# e-ink-clock.net
KiCad netlist of a schematic drawn in EAGLE
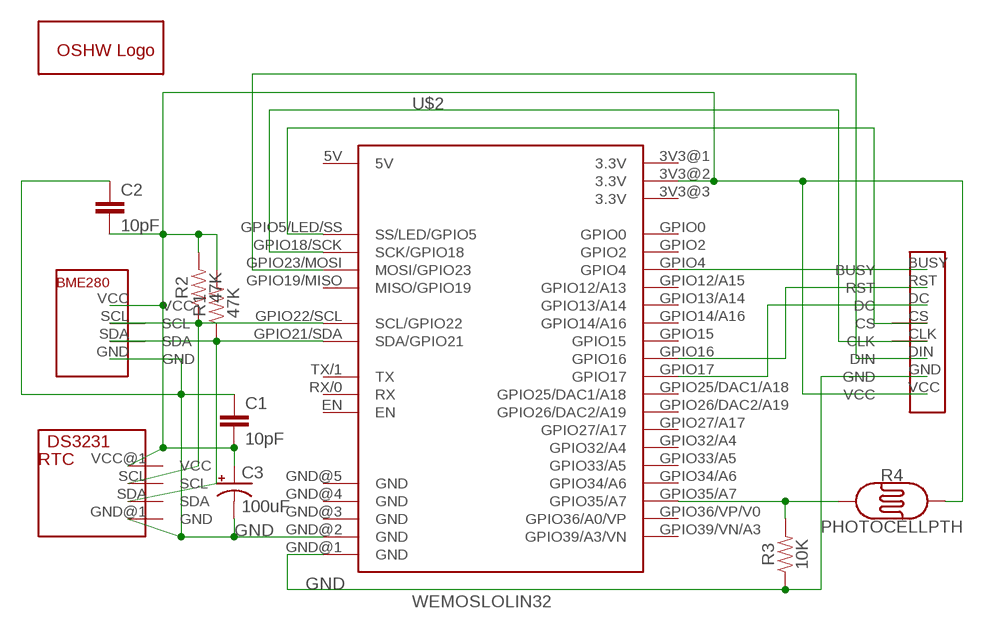
[diagram p0: schematic, sheet 1]

(export (version "E")
  (design (tool "Eeschema 10.0.6"))
  (components
    (comp (ref "C1")
      (value "10pF")
      (footprint "eagle-import:CAP-PTH-SMALL2")
      (libsource (lib "eagle-import") (part "CAPPTH2"))
    )
    (comp (ref "C2")
      (value "10pF")
      (footprint "eagle-import:CAP-PTH-SMALL2")
      (libsource (lib "eagle-import") (part "CAPPTH2"))
    )
    (comp (ref "C3")
      (value "100uF")
      (footprint "eagle-import:CPOL-RADIAL-2.5MM-6.5MM")
      (libsource (lib "eagle-import") (part "100UF-POLAR-RADIAL-2.5MM-25V-20%"))
    )
    (comp (ref "GOLD_ORB_SM1")
      (value "OSHWLOGOLOGO16MM")
      (footprint "eagle-import:OSHW_16MM")
      (libsource (lib "eagle-import") (part "OSHWLOGOLOGO16MM"))
    )
    (comp (ref "R1")
      (value "47K")
      (footprint "eagle-import:AXIAL-0.3")
      (libsource (lib "eagle-import") (part "RESISTORAXIAL-0.3"))
    )
    (comp (ref "R2")
      (value "47K")
      (footprint "eagle-import:AXIAL-0.3")
      (libsource (lib "eagle-import") (part "RESISTORAXIAL-0.3"))
    )
    (comp (ref "R3")
      (value "10K")
      (footprint "eagle-import:AXIAL-0.3")
      (libsource (lib "eagle-import") (part "RESISTORAXIAL-0.3"))
    )
    (comp (ref "R4")
      (value "PHOTOCELLPTH")
      (footprint "eagle-import:PHOTOCELL")
      (libsource (lib "eagle-import") (part "PHOTOCELLPTH"))
    )
    (comp (ref "U$1")
      (value "WAVESHAREE-INK")
      (footprint "eagle-import:WAVESHARE-EINK")
      (libsource (lib "eagle-import") (part "WAVESHAREE-INK"))
    )
    (comp (ref "U$2")
      (value "WEMOSLOLIN32")
      (footprint "eagle-import:LOLIN32VAR1")
      (libsource (lib "eagle-import") (part "WEMOSLOLIN32"))
    )
    (comp (ref "U$3")
      (value "BME280BREAKOUTBME280")
      (footprint "eagle-import:HDRV4W64P254_1X4_1016X508X838B")
      (libsource (lib "eagle-import") (part "BME280BREAKOUTBME280"))
    )
    (comp (ref "U$4")
      (value "DS3231BREAKOUT")
      (footprint "eagle-import:DS3231BREAKOUT")
      (libsource (lib "eagle-import") (part "DS3231BREAKOUT"))
    )
  )
  (nets
    (net (code "1") (name "/3.3V") (class "Default")
      (node (ref "U$2") (pin "3V3@3") (pinfunction "3.3V_3V3@3") (pintype "power_in"))
    )
    (net (code "2") (name "/5V") (class "Default")
      (node (ref "U$2") (pin "5V") (pinfunction "5V_5V") (pintype "power_in"))
    )
    (net (code "3") (name "/GND") (class "Default")
      (node (ref "C1") (pin "1") (pinfunction "1_1") (pintype "passive"))
      (node (ref "C2") (pin "1") (pinfunction "1_1") (pintype "passive"))
      (node (ref "C3") (pin "2") (pinfunction "-_2") (pintype "passive"))
      (node (ref "R3") (pin "P$1") (pinfunction "1_P$1") (pintype "passive"))
      (node (ref "U$1") (pin "GND") (pinfunction "GND_GND") (pintype "power_in"))
      (node (ref "U$2") (pin "GND@1") (pinfunction "GND_GND@1") (pintype "power_in"))
      (node (ref "U$2") (pin "GND@2") (pinfunction "GND_GND@2") (pintype "bidirectional"))
      (node (ref "U$3") (pin "GND") (pinfunction "GND_GND") (pintype "power_in"))
      (node (ref "U$4") (pin "GND@1") (pinfunction "GND_GND@1") (pintype "power_in"))
    )
    (net (code "4") (name "Net-(C3-+)") (class "Default")
      (node (ref "C1") (pin "2") (pinfunction "2_2") (pintype "passive"))
      (node (ref "C2") (pin "2") (pinfunction "2_2") (pintype "passive"))
      (node (ref "C3") (pin "1") (pinfunction "+_1") (pintype "passive"))
      (node (ref "R1") (pin "P$2") (pinfunction "2_P$2") (pintype "passive"))
      (node (ref "R2") (pin "P$2") (pinfunction "2_P$2") (pintype "passive"))
      (node (ref "R4") (pin "2") (pinfunction "P$2_2") (pintype "bidirectional"))
      (node (ref "U$1") (pin "VCC") (pinfunction "VCC_VCC") (pintype "power_in"))
      (node (ref "U$2") (pin "3V3@2") (pinfunction "3.3V_3V3@2") (pintype "bidirectional"))
      (node (ref "U$3") (pin "VCC") (pinfunction "VCC_VCC") (pintype "power_in"))
      (node (ref "U$4") (pin "VCC@1") (pinfunction "VCC_VCC@1") (pintype "power_in"))
    )
    (net (code "5") (name "Net-(R1-1)") (class "Default")
      (node (ref "R1") (pin "P$1") (pinfunction "1_P$1") (pintype "passive"))
      (node (ref "U$2") (pin "GPIO21/SDA") (pinfunction "SDA/GPIO21_GPIO21/SDA") (pintype "bidirectional"))
      (node (ref "U$3") (pin "SDA") (pinfunction "SDA_SDA") (pintype "bidirectional"))
      (node (ref "U$4") (pin "SDA") (pinfunction "SDA_SDA") (pintype "bidirectional"))
    )
    (net (code "6") (name "Net-(R2-1)") (class "Default")
      (node (ref "R2") (pin "P$1") (pinfunction "1_P$1") (pintype "passive"))
      (node (ref "U$2") (pin "GPIO22/SCL") (pinfunction "SCL/GPIO22_GPIO22/SCL") (pintype "bidirectional"))
      (node (ref "U$3") (pin "SCL") (pinfunction "SCL_SCL") (pintype "bidirectional"))
      (node (ref "U$4") (pin "SCL") (pinfunction "SCL_SCL") (pintype "bidirectional"))
    )
    (net (code "7") (name "Net-(R3-2)") (class "Default")
      (node (ref "R3") (pin "P$2") (pinfunction "2_P$2") (pintype "passive"))
      (node (ref "R4") (pin "1") (pinfunction "P$1_1") (pintype "bidirectional"))
      (node (ref "U$2") (pin "GPIO35/A7") (pinfunction "GPIO35/A7_GPIO35/A7") (pintype "bidirectional"))
    )
    (net (code "8") (name "Net-(U$1-PadBUSY)") (class "Default")
      (node (ref "U$1") (pin "BUSY") (pinfunction "BUSY_BUSY") (pintype "bidirectional"))
      (node (ref "U$2") (pin "GPIO4") (pinfunction "GPIO4_GPIO4") (pintype "bidirectional"))
    )
    (net (code "9") (name "Net-(U$1-PadDC)") (class "Default")
      (node (ref "U$1") (pin "DC") (pinfunction "DC_DC") (pintype "bidirectional"))
      (node (ref "U$2") (pin "GPIO17") (pinfunction "GPIO17_GPIO17") (pintype "bidirectional"))
    )
    (net (code "10") (name "Net-(U$1-PadRST)") (class "Default")
      (node (ref "U$1") (pin "RST") (pinfunction "RST_RST") (pintype "bidirectional"))
      (node (ref "U$2") (pin "GPIO16") (pinfunction "GPIO16_GPIO16") (pintype "bidirectional"))
    )
    (net (code "11") (name "Net-(U$2-MOSI{slash}GPIO23)") (class "Default")
      (node (ref "U$1") (pin "DIN") (pinfunction "DIN_DIN") (pintype "bidirectional"))
      (node (ref "U$2") (pin "GPIO23/MOSI") (pinfunction "MOSI/GPIO23_GPIO23/MOSI") (pintype "bidirectional"))
    )
    (net (code "12") (name "Net-(U$2-SCK{slash}GPIO18)") (class "Default")
      (node (ref "U$1") (pin "CLK") (pinfunction "CLK_CLK") (pintype "bidirectional"))
      (node (ref "U$2") (pin "GPIO18/SCK") (pinfunction "SCK/GPIO18_GPIO18/SCK") (pintype "bidirectional"))
    )
    (net (code "13") (name "Net-(U$2-SS{slash}LED{slash}GPIO5)") (class "Default")
      (node (ref "U$1") (pin "CS") (pinfunction "CS_CS") (pintype "bidirectional"))
      (node (ref "U$2") (pin "GPIO5/LED/SS") (pinfunction "SS/LED/GPIO5_GPIO5/LED/SS") (pintype "bidirectional"))
    )
    (net (code "14") (name "unconnected-(U$2-3.3V-Pad3V3@1)") (class "Default")
      (node (ref "U$2") (pin "3V3@1") (pinfunction "3.3V_3V3@1") (pintype "bidirectional"))
    )
    (net (code "15") (name "unconnected-(U$2-GND-PadGND@3)") (class "Default")
      (node (ref "U$2") (pin "GND@3") (pinfunction "GND_GND@3") (pintype "bidirectional"))
    )
    (net (code "16") (name "unconnected-(U$2-GND-PadGND@4)") (class "Default")
      (node (ref "U$2") (pin "GND@4") (pinfunction "GND_GND@4") (pintype "bidirectional"))
    )
    (net (code "17") (name "unconnected-(U$2-GND-PadGND@5)") (class "Default")
      (node (ref "U$2") (pin "GND@5") (pinfunction "GND_GND@5") (pintype "bidirectional"))
    )
    (net (code "18") (name "unconnected-(U$2-GPIO12{slash}A13-PadGPIO12{slash}A15)") (class "Default")
      (node (ref "U$2") (pin "GPIO12/A15") (pinfunction "GPIO12/A13_GPIO12/A15") (pintype "bidirectional"))
    )
    (net (code "19") (name "unconnected-(U$2-GPIO36{slash}A0{slash}VP-PadGPIO36{slash}VP{slash}V0)") (class "Default")
      (node (ref "U$2") (pin "GPIO36/VP/V0") (pinfunction "GPIO36/A0/VP_GPIO36/VP/V0") (pintype "bidirectional"))
    )
    (net (code "20") (name "unconnected-(U$2-GPIO39{slash}A3{slash}VN-PadGPIO39{slash}VN{slash}A3)") (class "Default")
      (node (ref "U$2") (pin "GPIO39/VN/A3") (pinfunction "GPIO39/A3/VN_GPIO39/VN/A3") (pintype "bidirectional"))
    )
    (net (code "21") (name "unconnected-(U$2-MISO{slash}GPIO19-PadGPIO19{slash}MISO)") (class "Default")
      (node (ref "U$2") (pin "GPIO19/MISO") (pinfunction "MISO/GPIO19_GPIO19/MISO") (pintype "bidirectional"))
    )
    (net (code "22") (name "unconnected-(U$2-PadEN)") (class "Default")
      (node (ref "U$2") (pin "EN") (pinfunction "EN_EN") (pintype "bidirectional"))
    )
    (net (code "23") (name "unconnected-(U$2-PadGPIO0)") (class "Default")
      (node (ref "U$2") (pin "GPIO0") (pinfunction "GPIO0_GPIO0") (pintype "bidirectional"))
    )
    (net (code "24") (name "unconnected-(U$2-PadGPIO2)") (class "Default")
      (node (ref "U$2") (pin "GPIO2") (pinfunction "GPIO2_GPIO2") (pintype "bidirectional"))
    )
    (net (code "25") (name "unconnected-(U$2-PadGPIO13{slash}A14)") (class "Default")
      (node (ref "U$2") (pin "GPIO13/A14") (pinfunction "GPIO13/A14_GPIO13/A14") (pintype "bidirectional"))
    )
    (net (code "26") (name "unconnected-(U$2-PadGPIO14{slash}A16)") (class "Default")
      (node (ref "U$2") (pin "GPIO14/A16") (pinfunction "GPIO14/A16_GPIO14/A16") (pintype "bidirectional"))
    )
    (net (code "27") (name "unconnected-(U$2-PadGPIO15)") (class "Default")
      (node (ref "U$2") (pin "GPIO15") (pinfunction "GPIO15_GPIO15") (pintype "bidirectional"))
    )
    (net (code "28") (name "unconnected-(U$2-PadGPIO25{slash}DAC1{slash}A18)") (class "Default")
      (node (ref "U$2") (pin "GPIO25/DAC1/A18") (pinfunction "GPIO25/DAC1/A18_GPIO25/DAC1/A18") (pintype "bidirectional"))
    )
    (net (code "29") (name "unconnected-(U$2-PadGPIO26{slash}DAC2{slash}A19)") (class "Default")
      (node (ref "U$2") (pin "GPIO26/DAC2/A19") (pinfunction "GPIO26/DAC2/A19_GPIO26/DAC2/A19") (pintype "bidirectional"))
    )
    (net (code "30") (name "unconnected-(U$2-PadGPIO27{slash}A17)") (class "Default")
      (node (ref "U$2") (pin "GPIO27/A17") (pinfunction "GPIO27/A17_GPIO27/A17") (pintype "bidirectional"))
    )
    (net (code "31") (name "unconnected-(U$2-PadGPIO32{slash}A4)") (class "Default")
      (node (ref "U$2") (pin "GPIO32/A4") (pinfunction "GPIO32/A4_GPIO32/A4") (pintype "bidirectional"))
    )
    (net (code "32") (name "unconnected-(U$2-PadGPIO33{slash}A5)") (class "Default")
      (node (ref "U$2") (pin "GPIO33/A5") (pinfunction "GPIO33/A5_GPIO33/A5") (pintype "bidirectional"))
    )
    (net (code "33") (name "unconnected-(U$2-PadGPIO34{slash}A6)") (class "Default")
      (node (ref "U$2") (pin "GPIO34/A6") (pinfunction "GPIO34/A6_GPIO34/A6") (pintype "bidirectional"))
    )
    (net (code "34") (name "unconnected-(U$2-RX-PadRX{slash}0)") (class "Default")
      (node (ref "U$2") (pin "RX/0") (pinfunction "RX_RX/0") (pintype "input"))
    )
    (net (code "35") (name "unconnected-(U$2-TX-PadTX{slash}1)") (class "Default")
      (node (ref "U$2") (pin "TX/1") (pinfunction "TX_TX/1") (pintype "output"))
    )
  )
)
